# Interface.net
KiCad netlist of a schematic drawn in Altium Designer
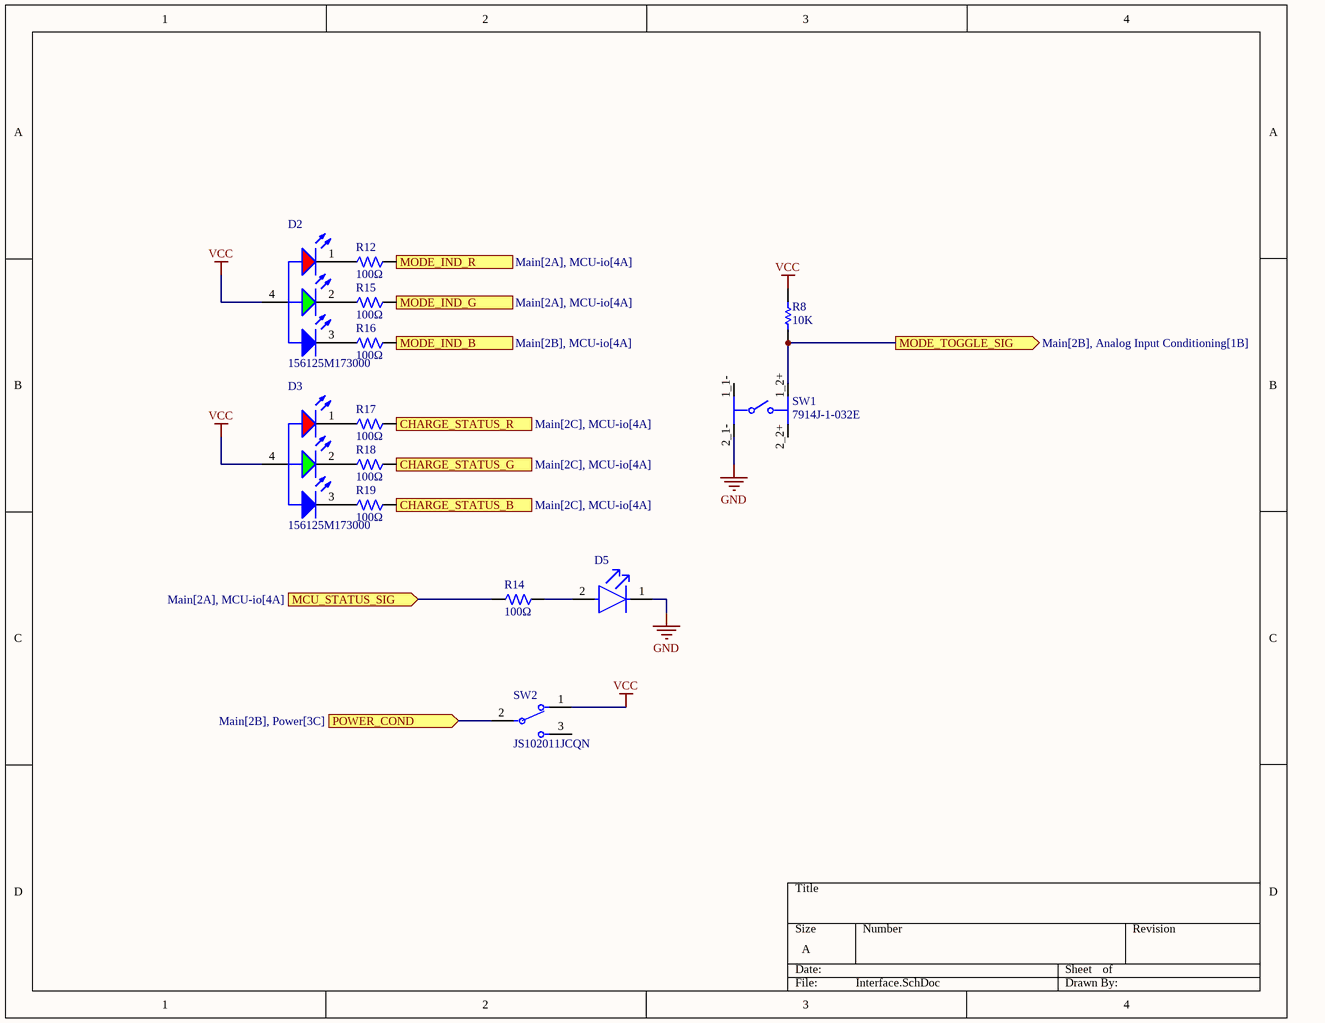
[diagram p0: Interface.SchDoc]

(export (version "E")
  (design (tool "Eeschema 10.0.6"))
  (components
    (comp (ref "D2")
      (value "156125M173000")
      (footprint "WL-SFRW_1205_reverse use")
      (description "LED RGB CLEAR 4SMD BOTTOM ENTRY")
      (libsource (lib "Altium Content Vault") (part "WL-SFRW_1205"))
    )
    (comp (ref "D3")
      (value "156125M173000")
      (footprint "WL-SFRW_1205_reverse use")
      (description "LED RGB CLEAR 4SMD BOTTOM ENTRY")
      (libsource (lib "Altium Content Vault") (part "WL-SFRW_1205"))
    )
    (comp (ref "D5")
      (value "LTST-C193TBKT-5A")
      (footprint "FP-LTST-C193TBKT-5A-MFG")
      (description "LED BLUE CLEAR CHIP SMD")
      (libsource (lib "Altium Content Vault") (part "8706943c75ba83719d021d2fdc84c58"))
    )
    (comp (ref "R8")
      (value "10K")
      (footprint "RES_SM0603_YAGEORC_N")
      (description "RES 10K SM0603 YAGEO RC_L")
      (fields
        (field (name "MANUFACTURER") "Yageo")
        (field (name "MANUFACTURER PART NUMBER") "RC0603FR-0710KL")
      )
      (libsource (lib "ResistorCapsInductors") (part "RC0603FR-0710KL"))
    )
    (comp (ref "R12")
      (value "0603WAF1000T5E")
      (footprint "RES-0603")
      (description "Resistor, 100Ω, ±1%, 100mW, 75V, ±200ppm/℃, -55℃~+155℃, SMD 0603")
      (fields
        (field (name "MANUFACTURER") "Uniroyal")
        (field (name "JLCPCB PART NUMBER") "C22775")
        (field (name "RESISTANCE") "100Ω")
      )
      (libsource (lib "JLCResistor") (part "0603WAF1000T5E"))
    )
    (comp (ref "R14")
      (value "0603WAF1000T5E")
      (footprint "RES-0603")
      (description "Resistor, 100Ω, ±1%, 100mW, 75V, ±200ppm/℃, -55℃~+155℃, SMD 0603")
      (fields
        (field (name "MANUFACTURER") "Uniroyal")
        (field (name "JLCPCB PART NUMBER") "C22775")
        (field (name "RESISTANCE") "100Ω")
      )
      (libsource (lib "JLCResistor") (part "0603WAF1000T5E"))
    )
    (comp (ref "R15")
      (value "0603WAF1000T5E")
      (footprint "RES-0603")
      (description "Resistor, 100Ω, ±1%, 100mW, 75V, ±200ppm/℃, -55℃~+155℃, SMD 0603")
      (fields
        (field (name "MANUFACTURER") "Uniroyal")
        (field (name "JLCPCB PART NUMBER") "C22775")
        (field (name "RESISTANCE") "100Ω")
      )
      (libsource (lib "JLCResistor") (part "0603WAF1000T5E"))
    )
    (comp (ref "R16")
      (value "0603WAF1000T5E")
      (footprint "RES-0603")
      (description "Resistor, 100Ω, ±1%, 100mW, 75V, ±200ppm/℃, -55℃~+155℃, SMD 0603")
      (fields
        (field (name "MANUFACTURER") "Uniroyal")
        (field (name "JLCPCB PART NUMBER") "C22775")
        (field (name "RESISTANCE") "100Ω")
      )
      (libsource (lib "JLCResistor") (part "0603WAF1000T5E"))
    )
    (comp (ref "R17")
      (value "0603WAF1000T5E")
      (footprint "RES-0603")
      (description "Resistor, 100Ω, ±1%, 100mW, 75V, ±200ppm/℃, -55℃~+155℃, SMD 0603")
      (fields
        (field (name "MANUFACTURER") "Uniroyal")
        (field (name "JLCPCB PART NUMBER") "C22775")
        (field (name "RESISTANCE") "100Ω")
      )
      (libsource (lib "JLCResistor") (part "0603WAF1000T5E"))
    )
    (comp (ref "R18")
      (value "0603WAF1000T5E")
      (footprint "RES-0603")
      (description "Resistor, 100Ω, ±1%, 100mW, 75V, ±200ppm/℃, -55℃~+155℃, SMD 0603")
      (fields
        (field (name "MANUFACTURER") "Uniroyal")
        (field (name "JLCPCB PART NUMBER") "C22775")
        (field (name "RESISTANCE") "100Ω")
      )
      (libsource (lib "JLCResistor") (part "0603WAF1000T5E"))
    )
    (comp (ref "R19")
      (value "0603WAF1000T5E")
      (footprint "RES-0603")
      (description "Resistor, 100Ω, ±1%, 100mW, 75V, ±200ppm/℃, -55℃~+155℃, SMD 0603")
      (fields
        (field (name "MANUFACTURER") "Uniroyal")
        (field (name "JLCPCB PART NUMBER") "C22775")
        (field (name "RESISTANCE") "100Ω")
      )
      (libsource (lib "JLCResistor") (part "0603WAF1000T5E"))
    )
    (comp (ref "SW1")
      (value "7914J-1-032E")
      (footprint "FP-7914J-1-032E-MFG")
      (description "SWITCH TACTILE SPST-NO 0.1A 16V")
      (libsource (lib "Altium Content Vault") (part "31b61e1575766857d5d37af9ed38f2e"))
    )
    (comp (ref "SW2")
      (value "JS102011JCQN")
      (footprint "FP-JS102011JCQN-MFG")
      (description "SWITCH SLIDE SPDT 300MA 6V")
      (libsource (lib "Altium Content Vault") (part "52c419afdc2a387c7d548259a9aeefb"))
    )
  )
  (nets
    (net (code "1") (name "/CHARGE_STATUS_B") (class "Default")
      (node (ref "R19") (pin "2") (pinfunction "2_2") (pintype "passive"))
    )
    (net (code "2") (name "/CHARGE_STATUS_G") (class "Default")
      (node (ref "R18") (pin "2") (pinfunction "2_2") (pintype "passive"))
    )
    (net (code "3") (name "/CHARGE_STATUS_R") (class "Default")
      (node (ref "R17") (pin "2") (pinfunction "2_2") (pintype "passive"))
    )
    (net (code "4") (name "/MCU_STATUS_SIG") (class "Default")
      (node (ref "R14") (pin "1") (pinfunction "1_1") (pintype "passive"))
    )
    (net (code "5") (name "/MODE_IND_B") (class "Default")
      (node (ref "R16") (pin "2") (pinfunction "2_2") (pintype "passive"))
    )
    (net (code "6") (name "/MODE_IND_G") (class "Default")
      (node (ref "R15") (pin "2") (pinfunction "2_2") (pintype "passive"))
    )
    (net (code "7") (name "/MODE_IND_R") (class "Default")
      (node (ref "R12") (pin "2") (pinfunction "2_2") (pintype "passive"))
    )
    (net (code "8") (name "/MODE_TOGGLE_SIG") (class "Default")
      (node (ref "R8") (pin "1") (pinfunction "1_1") (pintype "passive"))
      (node (ref "SW1") (pin "1_2+") (pinfunction "1_2+_1_2+") (pintype "passive"))
    )
    (net (code "9") (name "/POWER_COND") (class "Default")
      (node (ref "SW2") (pin "2") (pinfunction "2_2") (pintype "passive"))
    )
    (net (code "10") (name "GND") (class "Default")
      (node (ref "D5") (pin "1") (pinfunction "C_1") (pintype "passive"))
      (node (ref "SW1") (pin "2_1-") (pinfunction "2_1-_2_1-") (pintype "passive"))
    )
    (net (code "11") (name "Net-(D2-K-Pad1)") (class "Default")
      (node (ref "D2") (pin "1") (pinfunction "K_1") (pintype "passive"))
      (node (ref "R12") (pin "1") (pinfunction "1_1") (pintype "passive"))
    )
    (net (code "12") (name "Net-(D2-K-Pad2)") (class "Default")
      (node (ref "D2") (pin "2") (pinfunction "K_2") (pintype "passive"))
      (node (ref "R15") (pin "1") (pinfunction "1_1") (pintype "passive"))
    )
    (net (code "13") (name "Net-(D2-K-Pad3)") (class "Default")
      (node (ref "D2") (pin "3") (pinfunction "K_3") (pintype "passive"))
      (node (ref "R16") (pin "1") (pinfunction "1_1") (pintype "passive"))
    )
    (net (code "14") (name "Net-(D3-K-Pad1)") (class "Default")
      (node (ref "D3") (pin "1") (pinfunction "K_1") (pintype "passive"))
      (node (ref "R17") (pin "1") (pinfunction "1_1") (pintype "passive"))
    )
    (net (code "15") (name "Net-(D3-K-Pad2)") (class "Default")
      (node (ref "D3") (pin "2") (pinfunction "K_2") (pintype "passive"))
      (node (ref "R18") (pin "1") (pinfunction "1_1") (pintype "passive"))
    )
    (net (code "16") (name "Net-(D3-K-Pad3)") (class "Default")
      (node (ref "D3") (pin "3") (pinfunction "K_3") (pintype "passive"))
      (node (ref "R19") (pin "1") (pinfunction "1_1") (pintype "passive"))
    )
    (net (code "17") (name "Net-(D5-A)") (class "Default")
      (node (ref "D5") (pin "2") (pinfunction "A_2") (pintype "passive"))
      (node (ref "R14") (pin "2") (pinfunction "2_2") (pintype "passive"))
    )
    (net (code "18") (name "VCC") (class "Default")
      (node (ref "D2") (pin "4") (pinfunction "A_4") (pintype "passive"))
      (node (ref "D3") (pin "4") (pinfunction "A_4") (pintype "passive"))
      (node (ref "R8") (pin "2") (pinfunction "2_2") (pintype "passive"))
      (node (ref "SW2") (pin "1") (pinfunction "1_1") (pintype "passive"))
    )
    (net (code "19") (name "unconnected-(SW1-Pad1_1-)") (class "Default")
      (node (ref "SW1") (pin "1_1-") (pinfunction "1_1-_1_1-") (pintype "passive"))
    )
    (net (code "20") (name "unconnected-(SW1-Pad2_2+)") (class "Default")
      (node (ref "SW1") (pin "2_2+") (pinfunction "2_2+_2_2+") (pintype "passive"))
    )
    (net (code "21") (name "unconnected-(SW2-Pad3)") (class "Default")
      (node (ref "SW2") (pin "3") (pinfunction "3_3") (pintype "passive"))
    )
  )
)
